# tachometer.net
KiCad netlist of a schematic drawn in EAGLE
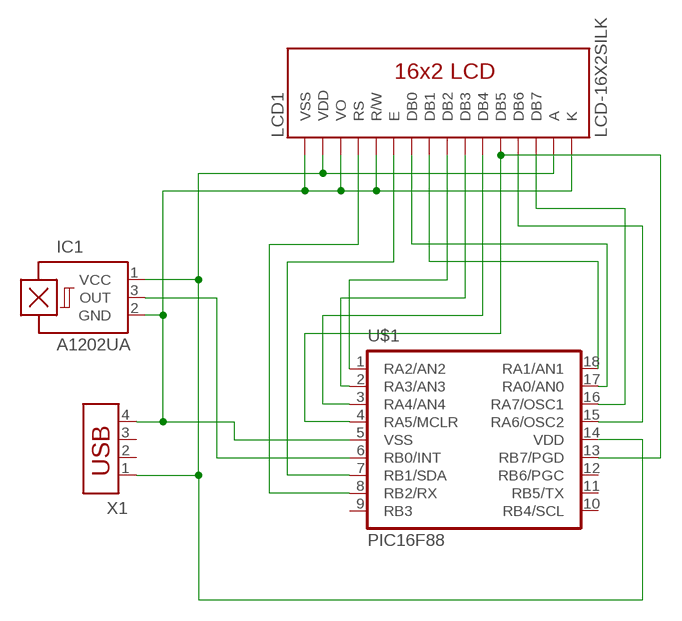
[diagram p0: schematic, sheet 1]

(export (version "E")
  (design (tool "Eeschema 10.0.6"))
  (components
    (comp (ref "IC1")
      (value "A1202UA")
      (footprint "eagle-import:SIP3-UA")
      (libsource (lib "eagle-import") (part "A12?UA02"))
    )
    (comp (ref "LCD1")
      (value "LCD-16X2SILK")
      (footprint "eagle-import:LCD-16X2")
      (libsource (lib "eagle-import") (part "LCD-16X2SILK"))
    )
    (comp (ref "U$1")
      (value "PIC16F88")
      (footprint "eagle-import:DIP18")
      (libsource (lib "eagle-import") (part "PIC16F88-DIP"))
    )
    (comp (ref "X1")
      (value "USB-787616")
      (footprint "eagle-import:USB")
      (libsource (lib "eagle-import") (part "USB-787616"))
    )
  )
  (nets
    (net (code "1") (name "Net-(IC1-GND)") (class "Default")
      (node (ref "IC1") (pin "2") (pinfunction "GND_2") (pintype "power_in"))
      (node (ref "LCD1") (pin "1") (pinfunction "VSS_1") (pintype "power_in"))
      (node (ref "LCD1") (pin "16") (pinfunction "K_16") (pintype "power_in"))
      (node (ref "LCD1") (pin "3") (pinfunction "VO_3") (pintype "bidirectional"))
      (node (ref "LCD1") (pin "5") (pinfunction "R/W_5") (pintype "input"))
      (node (ref "U$1") (pin "5") (pinfunction "VSS_5") (pintype "power_in"))
      (node (ref "X1") (pin "4") (pinfunction "4_4") (pintype "passive"))
    )
    (net (code "2") (name "Net-(IC1-OUT)") (class "Default")
      (node (ref "IC1") (pin "3") (pinfunction "OUT_3") (pintype "output"))
      (node (ref "U$1") (pin "6") (pinfunction "RB0/INT_6") (pintype "bidirectional"))
    )
    (net (code "3") (name "Net-(IC1-VCC)") (class "Default")
      (node (ref "IC1") (pin "1") (pinfunction "VCC_1") (pintype "power_in"))
      (node (ref "LCD1") (pin "15") (pinfunction "A_15") (pintype "power_in"))
      (node (ref "LCD1") (pin "2") (pinfunction "VDD_2") (pintype "power_in"))
      (node (ref "U$1") (pin "14") (pinfunction "VDD_14") (pintype "power_in"))
      (node (ref "X1") (pin "1") (pinfunction "1_1") (pintype "passive"))
    )
    (net (code "4") (name "Net-(LCD1-DB0)") (class "Default")
      (node (ref "LCD1") (pin "7") (pinfunction "DB0_7") (pintype "bidirectional"))
      (node (ref "U$1") (pin "17") (pinfunction "RA0/AN0_17") (pintype "bidirectional"))
    )
    (net (code "5") (name "Net-(LCD1-DB1)") (class "Default")
      (node (ref "LCD1") (pin "8") (pinfunction "DB1_8") (pintype "bidirectional"))
      (node (ref "U$1") (pin "18") (pinfunction "RA1/AN1_18") (pintype "bidirectional"))
    )
    (net (code "6") (name "Net-(LCD1-DB2)") (class "Default")
      (node (ref "LCD1") (pin "9") (pinfunction "DB2_9") (pintype "bidirectional"))
      (node (ref "U$1") (pin "1") (pinfunction "RA2/AN2_1") (pintype "bidirectional"))
    )
    (net (code "7") (name "Net-(LCD1-DB3)") (class "Default")
      (node (ref "LCD1") (pin "10") (pinfunction "DB3_10") (pintype "bidirectional"))
      (node (ref "U$1") (pin "2") (pinfunction "RA3/AN3_2") (pintype "bidirectional"))
    )
    (net (code "8") (name "Net-(LCD1-DB4)") (class "Default")
      (node (ref "LCD1") (pin "11") (pinfunction "DB4_11") (pintype "bidirectional"))
      (node (ref "U$1") (pin "3") (pinfunction "RA4/AN4_3") (pintype "bidirectional"))
    )
    (net (code "9") (name "Net-(LCD1-DB5)") (class "Default")
      (node (ref "LCD1") (pin "12") (pinfunction "DB5_12") (pintype "bidirectional"))
      (node (ref "U$1") (pin "13") (pinfunction "RB7/PGD_13") (pintype "bidirectional"))
      (node (ref "U$1") (pin "4") (pinfunction "RA5/MCLR_4") (pintype "input"))
    )
    (net (code "10") (name "Net-(LCD1-DB6)") (class "Default")
      (node (ref "LCD1") (pin "13") (pinfunction "DB6_13") (pintype "bidirectional"))
      (node (ref "U$1") (pin "15") (pinfunction "RA6/OSC2_15") (pintype "bidirectional"))
    )
    (net (code "11") (name "Net-(LCD1-DB7)") (class "Default")
      (node (ref "LCD1") (pin "14") (pinfunction "DB7_14") (pintype "bidirectional"))
      (node (ref "U$1") (pin "16") (pinfunction "RA7/OSC1_16") (pintype "bidirectional"))
    )
    (net (code "12") (name "Net-(LCD1-E)") (class "Default")
      (node (ref "LCD1") (pin "6") (pinfunction "E_6") (pintype "input"))
      (node (ref "U$1") (pin "7") (pinfunction "RB1/SDA_7") (pintype "bidirectional"))
    )
    (net (code "13") (name "Net-(LCD1-RS)") (class "Default")
      (node (ref "LCD1") (pin "4") (pinfunction "RS_4") (pintype "input"))
      (node (ref "U$1") (pin "8") (pinfunction "RB2/RX_8") (pintype "bidirectional"))
    )
    (net (code "14") (name "unconnected-(U$1-RB3-Pad9)") (class "Default")
      (node (ref "U$1") (pin "9") (pinfunction "RB3_9") (pintype "bidirectional"))
    )
    (net (code "15") (name "unconnected-(U$1-RB4{slash}SCL-Pad10)") (class "Default")
      (node (ref "U$1") (pin "10") (pinfunction "RB4/SCL_10") (pintype "bidirectional"))
    )
    (net (code "16") (name "unconnected-(U$1-RB5{slash}TX-Pad11)") (class "Default")
      (node (ref "U$1") (pin "11") (pinfunction "RB5/TX_11") (pintype "bidirectional"))
    )
    (net (code "17") (name "unconnected-(U$1-RB6{slash}PGC-Pad12)") (class "Default")
      (node (ref "U$1") (pin "12") (pinfunction "RB6/PGC_12") (pintype "bidirectional"))
    )
    (net (code "18") (name "unconnected-(X1-Pad2)") (class "Default")
      (node (ref "X1") (pin "2") (pinfunction "2_2") (pintype "passive"))
    )
    (net (code "19") (name "unconnected-(X1-Pad3)") (class "Default")
      (node (ref "X1") (pin "3") (pinfunction "3_3") (pintype "passive"))
    )
  )
)
